# Sheet2.net
KiCad netlist of a schematic drawn in Altium Designer
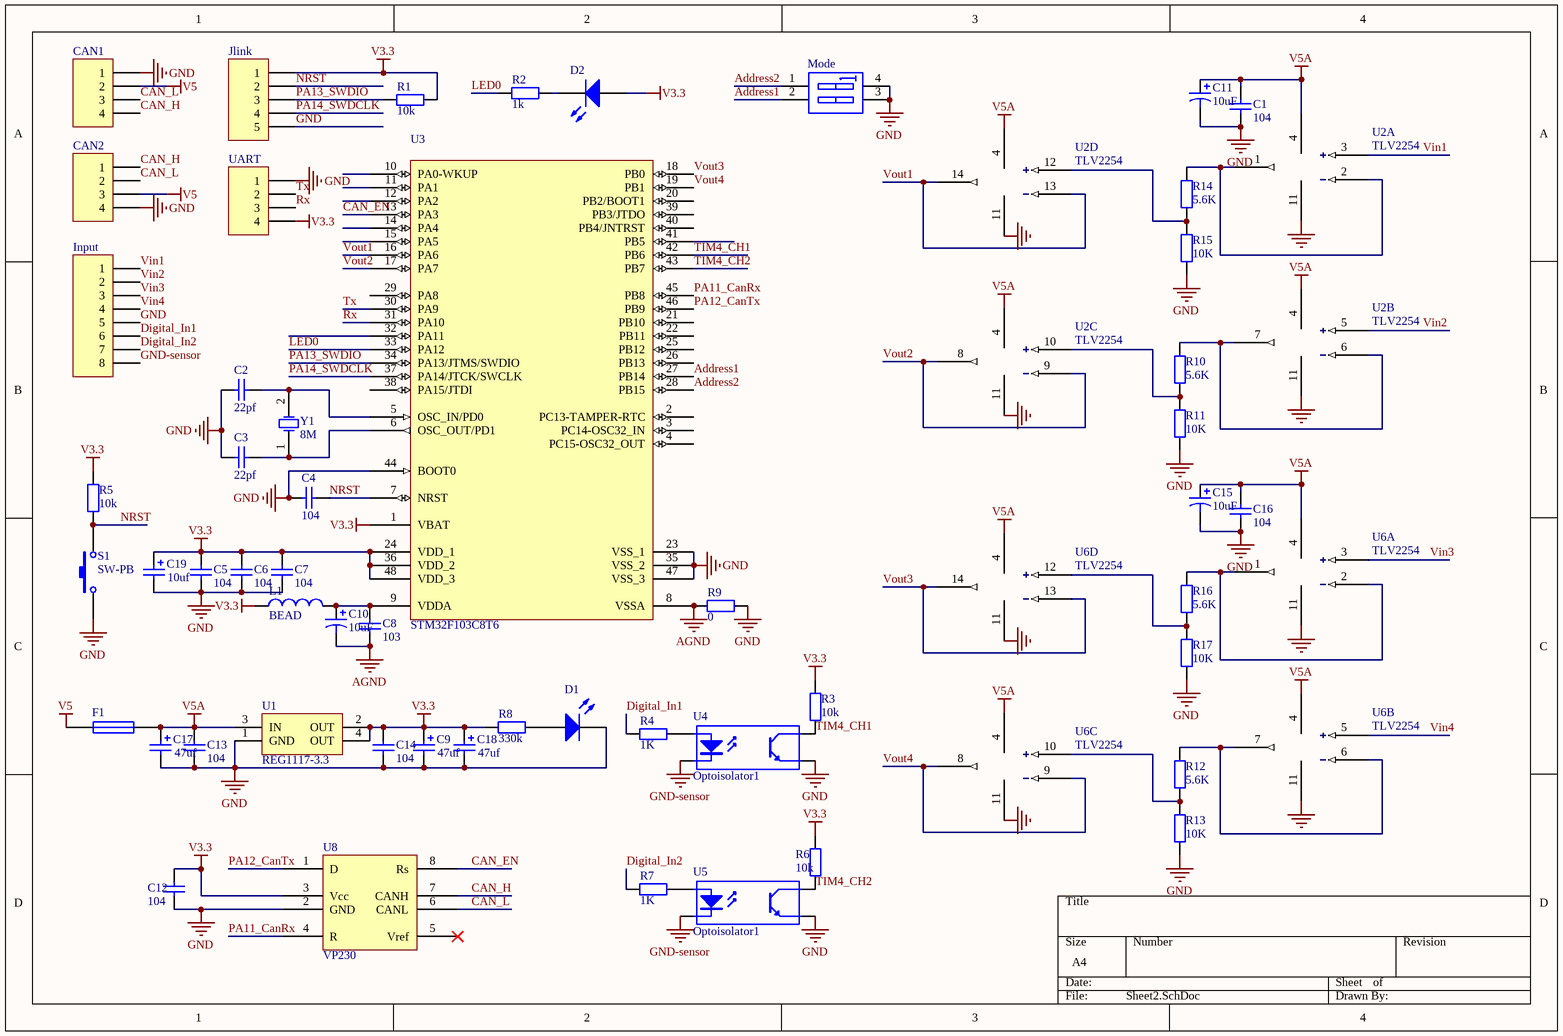
[diagram p0: Sheet2.SchDoc]

(export (version "E")
  (design (tool "Eeschema 10.0.6"))
  (components
    (comp (ref "C1")
      (value "104")
      (footprint "C0805")
      (description "Capacitor")
      (fields (field (name "Comment") "Cap") (field (name "PUBLISHER") "Altium Limited"))
      (libsource (lib "Miscellaneous Devices") (part "Cap"))
    )
    (comp (ref "C2")
      (value "22pf")
      (footprint "C0805")
      (description "Capacitor")
      (fields (field (name "Comment") "Cap") (field (name "PUBLISHER") "Altium Limited"))
      (libsource (lib "Miscellaneous Devices") (part "Cap"))
    )
    (comp (ref "C3")
      (value "22pf")
      (footprint "C0805")
      (description "Capacitor")
      (fields (field (name "Comment") "Cap") (field (name "PUBLISHER") "Altium Limited"))
      (libsource (lib "Miscellaneous Devices") (part "Cap"))
    )
    (comp (ref "C4")
      (value "104")
      (footprint "C0805")
      (description "Capacitor")
      (fields (field (name "Comment") "Cap") (field (name "PUBLISHER") "Altium Limited"))
      (libsource (lib "Miscellaneous Devices") (part "Cap"))
    )
    (comp (ref "C5")
      (value "104")
      (footprint "C0805")
      (description "Capacitor")
      (fields (field (name "Comment") "Cap") (field (name "PUBLISHER") "Altium Limited"))
      (libsource (lib "Miscellaneous Devices") (part "Cap"))
    )
    (comp (ref "C6")
      (value "104")
      (footprint "C0805")
      (description "Capacitor")
      (fields (field (name "Comment") "Cap") (field (name "PUBLISHER") "Altium Limited"))
      (libsource (lib "Miscellaneous Devices") (part "Cap"))
    )
    (comp (ref "C7")
      (value "104")
      (footprint "C0805")
      (description "Capacitor")
      (fields (field (name "Comment") "Cap") (field (name "PUBLISHER") "Altium Limited"))
      (libsource (lib "Miscellaneous Devices") (part "Cap"))
    )
    (comp (ref "C8")
      (value "103")
      (footprint "C0805")
      (description "Capacitor")
      (fields (field (name "Comment") "Cap") (field (name "PUBLISHER") "Altium Limited"))
      (libsource (lib "Miscellaneous Devices") (part "Cap"))
    )
    (comp (ref "C9")
      (value "47uf")
      (footprint "1812")
      (description "Polarized Capacitor (Axial)")
      (fields (field (name "Comment") "Cap Pol2") (field (name "PUBLISHER") "Altium Limited"))
      (libsource (lib "Miscellaneous Devices") (part "Cap Pol2"))
    )
    (comp (ref "C10")
      (value "10uF")
      (footprint "1206")
      (description "Polarized Capacitor (Radial)")
      (fields (field (name "Comment") "Cap Pol1") (field (name "PUBLISHER") "Altium Limited"))
      (libsource (lib "Miscellaneous Devices") (part "Cap Pol1"))
    )
    (comp (ref "C11")
      (value "10uF")
      (footprint "1206")
      (description "Polarized Capacitor (Radial)")
      (fields (field (name "Comment") "Cap Pol1") (field (name "PUBLISHER") "Altium Limited"))
      (libsource (lib "Miscellaneous Devices") (part "Cap Pol1"))
    )
    (comp (ref "C12")
      (value "104")
      (footprint "C0805")
      (description "Capacitor")
      (fields (field (name "Comment") "Cap") (field (name "PUBLISHER") "Altium Limited"))
      (libsource (lib "Miscellaneous Devices") (part "Cap"))
    )
    (comp (ref "C13")
      (value "104")
      (footprint "C0805")
      (description "Capacitor")
      (fields (field (name "Comment") "Cap") (field (name "PUBLISHER") "Altium Limited"))
      (libsource (lib "Miscellaneous Devices") (part "Cap"))
    )
    (comp (ref "C14")
      (value "104")
      (footprint "C0805")
      (description "Capacitor")
      (fields (field (name "Comment") "Cap") (field (name "PUBLISHER") "Altium Limited"))
      (libsource (lib "Miscellaneous Devices") (part "Cap"))
    )
    (comp (ref "C15")
      (value "10uF")
      (footprint "1206")
      (description "Polarized Capacitor (Radial)")
      (fields (field (name "Comment") "Cap Pol1") (field (name "PUBLISHER") "Altium Limited"))
      (libsource (lib "Miscellaneous Devices") (part "Cap Pol1"))
    )
    (comp (ref "C16")
      (value "104")
      (footprint "C0805")
      (description "Capacitor")
      (fields (field (name "Comment") "Cap") (field (name "PUBLISHER") "Altium Limited"))
      (libsource (lib "Miscellaneous Devices") (part "Cap"))
    )
    (comp (ref "C17")
      (value "47uf")
      (footprint "1812")
      (description "Polarized Capacitor (Axial)")
      (fields (field (name "Comment") "Cap Pol2") (field (name "PUBLISHER") "Altium Limited"))
      (libsource (lib "Miscellaneous Devices") (part "Cap Pol2"))
    )
    (comp (ref "C18")
      (value "47uf")
      (footprint "1812")
      (description "Polarized Capacitor (Axial)")
      (fields (field (name "Comment") "Cap Pol2") (field (name "PUBLISHER") "Altium Limited"))
      (libsource (lib "Miscellaneous Devices") (part "Cap Pol2"))
    )
    (comp (ref "C19")
      (value "10uf")
      (footprint "1206")
      (description "Polarized Capacitor (Axial)")
      (fields (field (name "Comment") "Cap Pol2") (field (name "PUBLISHER") "Altium Limited"))
      (libsource (lib "Miscellaneous Devices") (part "Cap Pol2"))
    )
    (comp (ref "CAN1")
      (value "Header 4")
      (footprint "DuraClik*4")
      (description "Header, 4-Pin")
      (fields (field (name "PUBLISHER") "Altium Limited"))
      (libsource (lib "Miscellaneous Connectors") (part "Header 4"))
    )
    (comp (ref "CAN2")
      (value "Header 4")
      (footprint "DuraClik*4")
      (description "Header, 4-Pin")
      (fields (field (name "PUBLISHER") "Altium Limited"))
      (libsource (lib "Miscellaneous Connectors") (part "Header 4"))
    )
    (comp (ref "D1")
      (value "LED2")
      (footprint "C0805")
      (description "Typical RED, GREEN, YELLOW, AMBER GaAs LED")
      (fields (field (name "PUBLISHER") "Altium Limited"))
      (libsource (lib "Miscellaneous Devices") (part "LED2"))
    )
    (comp (ref "D2")
      (value "LED2")
      (footprint "C0805")
      (description "Typical RED, GREEN, YELLOW, AMBER GaAs LED")
      (fields (field (name "PUBLISHER") "Altium Limited"))
      (libsource (lib "Miscellaneous Devices") (part "LED2"))
    )
    (comp (ref "F1")
      (value "Fuse 1")
      (footprint "1812")
      (description "Fuse")
      (fields (field (name "PUBLISHER") "Altium Limited"))
      (libsource (lib "Miscellaneous Devices") (part "Fuse 1"))
    )
    (comp (ref "Input")
      (value "Header 8")
      (footprint "DuraClik*8")
      (description "Header, 8-Pin")
      (fields (field (name "PUBLISHER") "Altium Limited"))
      (libsource (lib "Miscellaneous Connectors") (part "Header 8"))
    )
    (comp (ref "Jlink")
      (value "Jlink")
      (footprint "HDR1X5")
      (description "Header, 5-Pin")
      (fields (field (name "PUBLISHER") "Altium Limited"))
      (libsource (lib "Miscellaneous Connectors") (part "Header 5"))
    )
    (comp (ref "L1")
      (value "BEAD")
      (footprint "C0805")
      (description "Inductor")
      (fields (field (name "PUBLISHER") "Altium Limited"))
      (libsource (lib "Miscellaneous Devices") (part "Inductor"))
    )
    (comp (ref "Mode")
      (value "SW DIP-2")
      (footprint "DIP-4")
      (description "DIP Switch, 2 Position, SPST")
      (fields (field (name "PUBLISHER") "Altium Limited"))
      (libsource (lib "Miscellaneous Devices") (part "SW DIP-2"))
    )
    (comp (ref "R1")
      (value "10k")
      (footprint "C0805")
      (description "Resistor")
      (fields (field (name "Comment") "Res2") (field (name "PUBLISHER") "Altium Limited"))
      (libsource (lib "") (part "Res2_2"))
    )
    (comp (ref "R2")
      (value "1k")
      (footprint "C0805")
      (description "Resistor")
      (fields (field (name "Comment") "Res2") (field (name "PUBLISHER") "Altium Limited"))
      (libsource (lib "") (part "Res2_2"))
    )
    (comp (ref "R3")
      (value "10k")
      (footprint "C0805")
      (description "Resistor")
      (fields (field (name "Comment") "Res2") (field (name "PUBLISHER") "Altium Limited"))
      (libsource (lib "") (part "Res2_3"))
    )
    (comp (ref "R4")
      (value "1K")
      (footprint "C0805")
      (description "Resistor")
      (fields (field (name "Comment") "Res2") (field (name "PUBLISHER") "Altium Limited"))
      (libsource (lib "") (part "Res2_1"))
    )
    (comp (ref "R5")
      (value "10k")
      (footprint "C0805")
      (description "Resistor")
      (fields (field (name "Comment") "Res2") (field (name "PUBLISHER") "Altium Limited"))
      (libsource (lib "") (part "Res2_3"))
    )
    (comp (ref "R6")
      (value "10k")
      (footprint "C0805")
      (description "Resistor")
      (fields (field (name "Comment") "Res2") (field (name "PUBLISHER") "Altium Limited"))
      (libsource (lib "Miscellaneous Devices") (part "Res2"))
    )
    (comp (ref "R7")
      (value "1K")
      (footprint "C0805")
      (description "Resistor")
      (fields (field (name "Comment") "Res2") (field (name "PUBLISHER") "Altium Limited"))
      (libsource (lib "") (part "Res2_1"))
    )
    (comp (ref "R8")
      (value "330k")
      (footprint "C0805")
      (description "Resistor")
      (fields (field (name "Comment") "Res2") (field (name "PUBLISHER") "Altium Limited"))
      (libsource (lib "") (part "Res2_1"))
    )
    (comp (ref "R9")
      (value "0")
      (footprint "C0805")
      (description "Resistor")
      (fields (field (name "Comment") "Res2") (field (name "PUBLISHER") "Altium Limited"))
      (libsource (lib "") (part "Res2_1"))
    )
    (comp (ref "R10")
      (value "5.6K")
      (footprint "C0805")
      (description "Resistor")
      (fields (field (name "Comment") "Res2") (field (name "PUBLISHER") "Altium Limited"))
      (libsource (lib "Miscellaneous Devices") (part "Res2"))
    )
    (comp (ref "R11")
      (value "10K")
      (footprint "C0805")
      (description "Resistor")
      (fields (field (name "Comment") "Res2") (field (name "PUBLISHER") "Altium Limited"))
      (libsource (lib "Miscellaneous Devices") (part "Res2"))
    )
    (comp (ref "R12")
      (value "5.6K")
      (footprint "C0805")
      (description "Resistor")
      (fields (field (name "Comment") "Res2") (field (name "PUBLISHER") "Altium Limited"))
      (libsource (lib "Miscellaneous Devices") (part "Res2"))
    )
    (comp (ref "R13")
      (value "10K")
      (footprint "C0805")
      (description "Resistor")
      (fields (field (name "Comment") "Res2") (field (name "PUBLISHER") "Altium Limited"))
      (libsource (lib "Miscellaneous Devices") (part "Res2"))
    )
    (comp (ref "R14")
      (value "5.6K")
      (footprint "C0805")
      (description "Resistor")
      (fields (field (name "Comment") "Res2") (field (name "PUBLISHER") "Altium Limited"))
      (libsource (lib "Miscellaneous Devices") (part "Res2"))
    )
    (comp (ref "R15")
      (value "10K")
      (footprint "C0805")
      (description "Resistor")
      (fields (field (name "Comment") "Res2") (field (name "PUBLISHER") "Altium Limited"))
      (libsource (lib "Miscellaneous Devices") (part "Res2"))
    )
    (comp (ref "R16")
      (value "5.6K")
      (footprint "C0805")
      (description "Resistor")
      (fields (field (name "Comment") "Res2") (field (name "PUBLISHER") "Altium Limited"))
      (libsource (lib "Miscellaneous Devices") (part "Res2"))
    )
    (comp (ref "R17")
      (value "10K")
      (footprint "C0805")
      (description "Resistor")
      (fields (field (name "Comment") "Res2") (field (name "PUBLISHER") "Altium Limited"))
      (libsource (lib "Miscellaneous Devices") (part "Res2"))
    )
    (comp (ref "S1")
      (value "SW-PB")
      (footprint "button_SMD")
      (description "Switch")
      (fields (field (name "PUBLISHER") "Altium Limited"))
      (libsource (lib "Miscellaneous Devices") (part "SW-PB"))
    )
    (comp (ref "U1")
      (value "REG1117-3.3")
      (footprint "ZZ311")
      (description "800mA and 1A Low Dropout Positive Regulator 2.85V, 3.3V, 5V, and Adjustable")
      (fields (field (name "PUBLISHER") "Altium Limited"))
      (libsource (lib "BB Power Mgt Voltage Regulator") (part "REG1117-3.3"))
    )
    (comp (ref "U2") (value "TLV2254") (footprint "TSSOP14") (libsource (lib "can") (part "TLV2254")))
    (comp (ref "U3")
      (value "STM32F103C8T6")
      (footprint "LQFP48_N")
      (description "STM32 ARM-based 32-bit MCU with 64 Kbytes Flash, 48-pin LQFP, Industrial Temperature")
      (fields (field (name "PUBLISHER") "Altium Limited"))
      (libsource (lib "ST Microcontroller 32-Bit STM32") (part "STM32F103C8T6"))
    )
    (comp (ref "U4")
      (value "Optoisolator1")
      (footprint "SOP4-large")
      (description "4-Pin Phototransistor Optocoupler")
      (fields (field (name "PUBLISHER") "Altium Limited"))
      (libsource (lib "Miscellaneous Devices") (part "Optoisolator1"))
    )
    (comp (ref "U5")
      (value "Optoisolator1")
      (footprint "SOP4-large")
      (description "4-Pin Phototransistor Optocoupler")
      (fields (field (name "PUBLISHER") "Altium Limited"))
      (libsource (lib "Miscellaneous Devices") (part "Optoisolator1"))
    )
    (comp (ref "U6") (value "TLV2254") (footprint "TSSOP14") (libsource (lib "can") (part "TLV2254")))
    (comp (ref "U8")
      (value "VP230")
      (footprint "SOP127P600X175-8M")
      (description "3.3-VCANTRANSCEIVERS")
      (libsource (lib "can") (part "VP230"))
    )
    (comp (ref "UART")
      (value "Header 4")
      (footprint "HDR1X4")
      (description "Header, 4-Pin")
      (fields (field (name "PUBLISHER") "Altium Limited"))
      (libsource (lib "Miscellaneous Connectors") (part "Header 4"))
    )
    (comp (ref "Y1")
      (value "8M")
      (footprint "XTAL")
      (description "Crystal Oscillator")
      (fields (field (name "PUBLISHER") "Altium Limited"))
      (libsource (lib "Miscellaneous Devices") (part "XTAL"))
    )
  )
  (nets
    (net (code "1") (name "/Address1") (class "Default")
      (node (ref "Mode") (pin "2") (pinfunction "A2_2") (pintype "passive"))
      (node (ref "U3") (pin "27") (pinfunction "PB14_27") (pintype "bidirectional"))
    )
    (net (code "2") (name "/Address2") (class "Default")
      (node (ref "Mode") (pin "1") (pinfunction "A1_1") (pintype "passive"))
      (node (ref "U3") (pin "28") (pinfunction "PB15_28") (pintype "bidirectional"))
    )
    (net (code "3") (name "/CAN_EN") (class "Default")
      (node (ref "U3") (pin "13") (pinfunction "PA3_13") (pintype "bidirectional"))
      (node (ref "U8") (pin "8") (pinfunction "Rs_8") (pintype "passive"))
    )
    (net (code "4") (name "/CAN_H") (class "Default")
      (node (ref "CAN1") (pin "4") (pinfunction "4_4") (pintype "passive"))
      (node (ref "CAN2") (pin "1") (pinfunction "1_1") (pintype "passive"))
      (node (ref "U8") (pin "7") (pinfunction "CANH_7") (pintype "passive"))
    )
    (net (code "5") (name "/CAN_L") (class "Default")
      (node (ref "CAN1") (pin "3") (pinfunction "3_3") (pintype "passive"))
      (node (ref "CAN2") (pin "2") (pinfunction "2_2") (pintype "passive"))
      (node (ref "U8") (pin "6") (pinfunction "CANL_6") (pintype "passive"))
    )
    (net (code "6") (name "/Digital_In1") (class "Default")
      (node (ref "Input") (pin "6") (pinfunction "6_6") (pintype "passive"))
      (node (ref "R4") (pin "2") (pinfunction "2_2") (pintype "passive"))
    )
    (net (code "7") (name "/Digital_In2") (class "Default")
      (node (ref "Input") (pin "7") (pinfunction "7_7") (pintype "passive"))
      (node (ref "R7") (pin "2") (pinfunction "2_2") (pintype "passive"))
    )
    (net (code "8") (name "/LED0") (class "Default")
      (node (ref "R2") (pin "1") (pinfunction "1_1") (pintype "passive"))
      (node (ref "U3") (pin "33") (pinfunction "PA12_33") (pintype "bidirectional"))
    )
    (net (code "9") (name "/NRST") (class "Default")
      (node (ref "C4") (pin "2") (pinfunction "2_2") (pintype "passive"))
      (node (ref "Jlink") (pin "2") (pinfunction "2_2") (pintype "passive"))
      (node (ref "R5") (pin "2") (pinfunction "2_2") (pintype "passive"))
      (node (ref "S1") (pin "2") (pinfunction "2_2") (pintype "passive"))
      (node (ref "U3") (pin "7") (pinfunction "NRST_7") (pintype "bidirectional"))
    )
    (net (code "10") (name "/PA11_CanRx") (class "Default")
      (node (ref "U3") (pin "45") (pinfunction "PB8_45") (pintype "bidirectional"))
      (node (ref "U8") (pin "4") (pinfunction "R_4") (pintype "passive"))
    )
    (net (code "11") (name "/PA12_CanTx") (class "Default")
      (node (ref "U3") (pin "46") (pinfunction "PB9_46") (pintype "bidirectional"))
      (node (ref "U8") (pin "1") (pinfunction "D_1") (pintype "passive"))
    )
    (net (code "12") (name "/PA13_SWDIO") (class "Default")
      (node (ref "Jlink") (pin "3") (pinfunction "3_3") (pintype "passive"))
      (node (ref "R1") (pin "1") (pinfunction "1_1") (pintype "passive"))
      (node (ref "U3") (pin "34") (pinfunction "PA13/JTMS/SWDIO_34") (pintype "bidirectional"))
    )
    (net (code "13") (name "/PA14_SWDCLK") (class "Default")
      (node (ref "Jlink") (pin "4") (pinfunction "4_4") (pintype "passive"))
      (node (ref "U3") (pin "37") (pinfunction "PA14/JTCK/SWCLK_37") (pintype "bidirectional"))
    )
    (net (code "14") (name "/Rx") (class "Default")
      (node (ref "U3") (pin "31") (pinfunction "PA10_31") (pintype "bidirectional"))
      (node (ref "UART") (pin "3") (pinfunction "3_3") (pintype "passive"))
    )
    (net (code "15") (name "/TIM4_CH1") (class "Default")
      (node (ref "R3") (pin "2") (pinfunction "2_2") (pintype "passive"))
      (node (ref "U3") (pin "42") (pinfunction "PB6_42") (pintype "bidirectional"))
      (node (ref "U4") (pin "4") (pinfunction "C_4") (pintype "passive"))
    )
    (net (code "16") (name "/TIM4_CH2") (class "Default")
      (node (ref "R6") (pin "1") (pinfunction "1_1") (pintype "passive"))
      (node (ref "U3") (pin "43") (pinfunction "PB7_43") (pintype "bidirectional"))
      (node (ref "U5") (pin "4") (pinfunction "C_4") (pintype "passive"))
    )
    (net (code "17") (name "/Tx") (class "Default")
      (node (ref "U3") (pin "30") (pinfunction "PA9_30") (pintype "bidirectional"))
      (node (ref "UART") (pin "2") (pinfunction "2_2") (pintype "passive"))
    )
    (net (code "18") (name "/Vin1") (class "Default")
      (node (ref "Input") (pin "1") (pinfunction "1_1") (pintype "passive"))
      (node (ref "U2") (pin "3") (pinfunction "1IN+_3") (pintype "input"))
    )
    (net (code "19") (name "/Vin2") (class "Default")
      (node (ref "Input") (pin "2") (pinfunction "2_2") (pintype "passive"))
      (node (ref "U2") (pin "5") (pinfunction "2IN+_5") (pintype "input"))
    )
    (net (code "20") (name "/Vin3") (class "Default")
      (node (ref "Input") (pin "3") (pinfunction "3_3") (pintype "passive"))
      (node (ref "U6") (pin "3") (pinfunction "1IN+_3") (pintype "input"))
    )
    (net (code "21") (name "/Vin4") (class "Default")
      (node (ref "Input") (pin "4") (pinfunction "4_4") (pintype "passive"))
      (node (ref "U6") (pin "5") (pinfunction "2IN+_5") (pintype "input"))
    )
    (net (code "22") (name "/Vout1") (class "Default")
      (node (ref "U2") (pin "13") (pinfunction "4IN-_13") (pintype "input"))
      (node (ref "U2") (pin "14") (pinfunction "4OUT_14") (pintype "output"))
      (node (ref "U3") (pin "16") (pinfunction "PA6_16") (pintype "bidirectional"))
    )
    (net (code "23") (name "/Vout2") (class "Default")
      (node (ref "U2") (pin "8") (pinfunction "3OUT_8") (pintype "output"))
      (node (ref "U2") (pin "9") (pinfunction "3IN-_9") (pintype "input"))
      (node (ref "U3") (pin "17") (pinfunction "PA7_17") (pintype "bidirectional"))
    )
    (net (code "24") (name "/Vout3") (class "Default")
      (node (ref "U3") (pin "18") (pinfunction "PB0_18") (pintype "bidirectional"))
      (node (ref "U6") (pin "13") (pinfunction "4IN-_13") (pintype "input"))
      (node (ref "U6") (pin "14") (pinfunction "4OUT_14") (pintype "output"))
    )
    (net (code "25") (name "/Vout4") (class "Default")
      (node (ref "U3") (pin "19") (pinfunction "PB1_19") (pintype "bidirectional"))
      (node (ref "U6") (pin "8") (pinfunction "3OUT_8") (pintype "output"))
      (node (ref "U6") (pin "9") (pinfunction "3IN-_9") (pintype "input"))
    )
    (net (code "26") (name "AGND") (class "Default")
      (node (ref "C10") (pin "2") (pinfunction "2_2") (pintype "passive"))
      (node (ref "C8") (pin "2") (pinfunction "2_2") (pintype "passive"))
      (node (ref "R9") (pin "2") (pinfunction "2_2") (pintype "passive"))
      (node (ref "U3") (pin "8") (pinfunction "VSSA_8") (pintype "power_in"))
    )
    (net (code "27") (name "GND") (class "Default")
      (node (ref "C1") (pin "2") (pinfunction "2_2") (pintype "passive"))
      (node (ref "C11") (pin "2") (pinfunction "2_2") (pintype "passive"))
      (node (ref "C12") (pin "1") (pinfunction "1_1") (pintype "passive"))
      (node (ref "C13") (pin "2") (pinfunction "2_2") (pintype "passive"))
      (node (ref "C14") (pin "2") (pinfunction "2_2") (pintype "passive"))
      (node (ref "C15") (pin "2") (pinfunction "2_2") (pintype "passive"))
      (node (ref "C16") (pin "2") (pinfunction "2_2") (pintype "passive"))
      (node (ref "C17") (pin "2") (pinfunction "2_2") (pintype "passive"))
      (node (ref "C18") (pin "2") (pinfunction "2_2") (pintype "passive"))
      (node (ref "C19") (pin "2") (pinfunction "2_2") (pintype "passive"))
      (node (ref "C2") (pin "1") (pinfunction "1_1") (pintype "passive"))
      (node (ref "C3") (pin "1") (pinfunction "1_1") (pintype "passive"))
      (node (ref "C4") (pin "1") (pinfunction "1_1") (pintype "passive"))
      (node (ref "C5") (pin "2") (pinfunction "2_2") (pintype "passive"))
      (node (ref "C6") (pin "2") (pinfunction "2_2") (pintype "passive"))
      (node (ref "C7") (pin "2") (pinfunction "2_2") (pintype "passive"))
      (node (ref "C9") (pin "2") (pinfunction "2_2") (pintype "passive"))
      (node (ref "CAN1") (pin "1") (pinfunction "1_1") (pintype "passive"))
      (node (ref "CAN2") (pin "4") (pinfunction "4_4") (pintype "passive"))
      (node (ref "D1") (pin "2") (pinfunction "K_2") (pintype "passive"))
      (node (ref "Input") (pin "5") (pinfunction "5_5") (pintype "passive"))
      (node (ref "Jlink") (pin "5") (pinfunction "5_5") (pintype "passive"))
      (node (ref "Mode") (pin "3") (pinfunction "B2_3") (pintype "passive"))
      (node (ref "Mode") (pin "4") (pinfunction "B1_4") (pintype "passive"))
      (node (ref "R11") (pin "1") (pinfunction "1_1") (pintype "passive"))
      (node (ref "R13") (pin "1") (pinfunction "1_1") (pintype "passive"))
      (node (ref "R15") (pin "1") (pinfunction "1_1") (pintype "passive"))
      (node (ref "R17") (pin "1") (pinfunction "1_1") (pintype "passive"))
      (node (ref "R9") (pin "1") (pinfunction "1_1") (pintype "passive"))
      (node (ref "S1") (pin "1") (pinfunction "1_1") (pintype "passive"))
      (node (ref "U1") (pin "1") (pinfunction "GND_1") (pintype "power_in"))
      (node (ref "U2") (pin "11") (pinfunction "GND_11") (pintype "passive"))
      (node (ref "U3") (pin "23") (pinfunction "VSS_1_23") (pintype "power_in"))
      (node (ref "U3") (pin "35") (pinfunction "VSS_2_35") (pintype "power_in"))
      (node (ref "U3") (pin "44") (pinfunction "BOOT0_44") (pintype "input"))
      (node (ref "U3") (pin "47") (pinfunction "VSS_3_47") (pintype "power_in"))
      (node (ref "U4") (pin "3") (pinfunction "E_3") (pintype "passive"))
      (node (ref "U5") (pin "3") (pinfunction "E_3") (pintype "passive"))
      (node (ref "U6") (pin "11") (pinfunction "GND_11") (pintype "passive"))
      (node (ref "U8") (pin "2") (pinfunction "GND_2") (pintype "passive"))
      (node (ref "UART") (pin "1") (pinfunction "1_1") (pintype "passive"))
    )
    (net (code "28") (name "GND-sensor") (class "Default")
      (node (ref "Input") (pin "8") (pinfunction "8_8") (pintype "passive"))
      (node (ref "U4") (pin "2") (pinfunction "K_2") (pintype "passive"))
      (node (ref "U5") (pin "2") (pinfunction "K_2") (pintype "passive"))
    )
    (net (code "29") (name "Net-(D1-A)") (class "Default")
      (node (ref "D1") (pin "1") (pinfunction "A_1") (pintype "passive"))
      (node (ref "R8") (pin "1") (pinfunction "1_1") (pintype "passive"))
    )
    (net (code "30") (name "Net-(D2-K)") (class "Default")
      (node (ref "D2") (pin "2") (pinfunction "K_2") (pintype "passive"))
      (node (ref "R2") (pin "2") (pinfunction "2_2") (pintype "passive"))
    )
    (net (code "31") (name "Net-(U2A-1IN-)") (class "Default")
      (node (ref "R14") (pin "2") (pinfunction "2_2") (pintype "passive"))
      (node (ref "U2") (pin "1") (pinfunction "1OUT_1") (pintype "output"))
      (node (ref "U2") (pin "2") (pinfunction "1IN-_2") (pintype "input"))
    )
    (net (code "32") (name "Net-(U2B-2IN-)") (class "Default")
      (node (ref "R10") (pin "2") (pinfunction "2_2") (pintype "passive"))
      (node (ref "U2") (pin "6") (pinfunction "2IN-_6") (pintype "input"))
      (node (ref "U2") (pin "7") (pinfunction "2OUT_7") (pintype "output"))
    )
    (net (code "33") (name "Net-(U2C-3IN+)") (class "Default")
      (node (ref "R10") (pin "1") (pinfunction "1_1") (pintype "passive"))
      (node (ref "R11") (pin "2") (pinfunction "2_2") (pintype "passive"))
      (node (ref "U2") (pin "10") (pinfunction "3IN+_10") (pintype "input"))
    )
    (net (code "34") (name "Net-(U2D-4IN+)") (class "Default")
      (node (ref "R14") (pin "1") (pinfunction "1_1") (pintype "passive"))
      (node (ref "R15") (pin "2") (pinfunction "2_2") (pintype "passive"))
      (node (ref "U2") (pin "12") (pinfunction "4IN+_12") (pintype "input"))
    )
    (net (code "35") (name "Net-(U3-OSC_IN{slash}PD0)") (class "Default")
      (node (ref "C2") (pin "2") (pinfunction "2_2") (pintype "passive"))
      (node (ref "U3") (pin "5") (pinfunction "OSC_IN/PD0_5") (pintype "input"))
      (node (ref "Y1") (pin "2") (pinfunction "OSC2_2") (pintype "passive"))
    )
    (net (code "36") (name "Net-(U3-OSC_OUT{slash}PD1)") (class "Default")
      (node (ref "C3") (pin "2") (pinfunction "2_2") (pintype "passive"))
      (node (ref "U3") (pin "6") (pinfunction "OSC_OUT/PD1_6") (pintype "output"))
      (node (ref "Y1") (pin "1") (pinfunction "OSC1_1") (pintype "passive"))
    )
    (net (code "37") (name "Net-(U3-VDDA)") (class "Default")
      (node (ref "C10") (pin "1") (pinfunction "1_1") (pintype "passive"))
      (node (ref "C8") (pin "1") (pinfunction "1_1") (pintype "passive"))
      (node (ref "L1") (pin "2") (pinfunction "2_2") (pintype "passive"))
      (node (ref "U3") (pin "9") (pinfunction "VDDA_9") (pintype "power_in"))
    )
    (net (code "38") (name "Net-(U4-A)") (class "Default")
      (node (ref "R4") (pin "1") (pinfunction "1_1") (pintype "passive"))
      (node (ref "U4") (pin "1") (pinfunction "A_1") (pintype "passive"))
    )
    (net (code "39") (name "Net-(U5-A)") (class "Default")
      (node (ref "R7") (pin "1") (pinfunction "1_1") (pintype "passive"))
      (node (ref "U5") (pin "1") (pinfunction "A_1") (pintype "passive"))
    )
    (net (code "40") (name "Net-(U6A-1IN-)") (class "Default")
      (node (ref "R16") (pin "2") (pinfunction "2_2") (pintype "passive"))
      (node (ref "U6") (pin "1") (pinfunction "1OUT_1") (pintype "output"))
      (node (ref "U6") (pin "2") (pinfunction "1IN-_2") (pintype "input"))
    )
    (net (code "41") (name "Net-(U6B-2IN-)") (class "Default")
      (node (ref "R12") (pin "2") (pinfunction "2_2") (pintype "passive"))
      (node (ref "U6") (pin "6") (pinfunction "2IN-_6") (pintype "input"))
      (node (ref "U6") (pin "7") (pinfunction "2OUT_7") (pintype "output"))
    )
    (net (code "42") (name "Net-(U6C-3IN+)") (class "Default")
      (node (ref "R12") (pin "1") (pinfunction "1_1") (pintype "passive"))
      (node (ref "R13") (pin "2") (pinfunction "2_2") (pintype "passive"))
      (node (ref "U6") (pin "10") (pinfunction "3IN+_10") (pintype "input"))
    )
    (net (code "43") (name "Net-(U6D-4IN+)") (class "Default")
      (node (ref "R16") (pin "1") (pinfunction "1_1") (pintype "passive"))
      (node (ref "R17") (pin "2") (pinfunction "2_2") (pintype "passive"))
      (node (ref "U6") (pin "12") (pinfunction "4IN+_12") (pintype "input"))
    )
    (net (code "44") (name "V3.3") (class "Default")
      (node (ref "C12") (pin "2") (pinfunction "2_2") (pintype "passive"))
      (node (ref "C14") (pin "1") (pinfunction "1_1") (pintype "passive"))
      (node (ref "C18") (pin "1") (pinfunction "1_1") (pintype "passive"))
      (node (ref "C19") (pin "1") (pinfunction "1_1") (pintype "passive"))
      (node (ref "C5") (pin "1") (pinfunction "1_1") (pintype "passive"))
      (node (ref "C6") (pin "1") (pinfunction "1_1") (pintype "passive"))
      (node (ref "C7") (pin "1") (pinfunction "1_1") (pintype "passive"))
      (node (ref "C9") (pin "1") (pinfunction "1_1") (pintype "passive"))
      (node (ref "D2") (pin "1") (pinfunction "A_1") (pintype "passive"))
      (node (ref "Jlink") (pin "1") (pinfunction "1_1") (pintype "passive"))
      (node (ref "L1") (pin "1") (pinfunction "1_1") (pintype "passive"))
      (node (ref "R1") (pin "2") (pinfunction "2_2") (pintype "passive"))
      (node (ref "R3") (pin "1") (pinfunction "1_1") (pintype "passive"))
      (node (ref "R5") (pin "1") (pinfunction "1_1") (pintype "passive"))
      (node (ref "R6") (pin "2") (pinfunction "2_2") (pintype "passive"))
      (node (ref "R8") (pin "2") (pinfunction "2_2") (pintype "passive"))
      (node (ref "U1") (pin "2") (pinfunction "OUT_2") (pintype "power_in"))
      (node (ref "U1") (pin "4") (pinfunction "OUT_4") (pintype "power_in"))
      (node (ref "U3") (pin "1") (pinfunction "VBAT_1") (pintype "power_in"))
      (node (ref "U3") (pin "24") (pinfunction "VDD_1_24") (pintype "power_in"))
      (node (ref "U3") (pin "36") (pinfunction "VDD_2_36") (pintype "power_in"))
      (node (ref "U3") (pin "48") (pinfunction "VDD_3_48") (pintype "power_in"))
      (node (ref "U8") (pin "3") (pinfunction "Vcc_3") (pintype "passive"))
      (node (ref "UART") (pin "4") (pinfunction "4_4") (pintype "passive"))
    )
    (net (code "45") (name "V5") (class "Default")
      (node (ref "CAN1") (pin "2") (pinfunction "2_2") (pintype "passive"))
      (node (ref "CAN2") (pin "3") (pinfunction "3_3") (pintype "passive"))
      (node (ref "F1") (pin "2") (pinfunction "2_2") (pintype "passive"))
    )
    (net (code "46") (name "V5A") (class "Default")
      (node (ref "C1") (pin "1") (pinfunction "1_1") (pintype "passive"))
      (node (ref "C11") (pin "1") (pinfunction "1_1") (pintype "passive"))
      (node (ref "C13") (pin "1") (pinfunction "1_1") (pintype "passive"))
      (node (ref "C15") (pin "1") (pinfunction "1_1") (pintype "passive"))
      (node (ref "C16") (pin "1") (pinfunction "1_1") (pintype "passive"))
      (node (ref "C17") (pin "1") (pinfunction "1_1") (pintype "passive"))
      (node (ref "F1") (pin "1") (pinfunction "1_1") (pintype "passive"))
      (node (ref "U1") (pin "3") (pinfunction "IN_3") (pintype "power_in"))
      (node (ref "U2") (pin "4") (pinfunction "Vcc_4") (pintype "passive"))
      (node (ref "U6") (pin "4") (pinfunction "Vcc_4") (pintype "passive"))
    )
    (net (code "47") (name "unconnected-(U3-PA0-WKUP-Pad10)") (class "Default")
      (node (ref "U3") (pin "10") (pinfunction "PA0-WKUP_10") (pintype "bidirectional"))
    )
    (net (code "48") (name "unconnected-(U3-PA1-Pad11)") (class "Default")
      (node (ref "U3") (pin "11") (pinfunction "PA1_11") (pintype "bidirectional"))
    )
    (net (code "49") (name "unconnected-(U3-PA2-Pad12)") (class "Default")
      (node (ref "U3") (pin "12") (pinfunction "PA2_12") (pintype "bidirectional"))
    )
    (net (code "50") (name "unconnected-(U3-PA4-Pad14)") (class "Default")
      (node (ref "U3") (pin "14") (pinfunction "PA4_14") (pintype "bidirectional"))
    )
    (net (code "51") (name "unconnected-(U3-PA5-Pad15)") (class "Default")
      (node (ref "U3") (pin "15") (pinfunction "PA5_15") (pintype "bidirectional"))
    )
    (net (code "52") (name "unconnected-(U3-PA8-Pad29)") (class "Default")
      (node (ref "U3") (pin "29") (pinfunction "PA8_29") (pintype "bidirectional"))
    )
    (net (code "53") (name "unconnected-(U3-PA11-Pad32)") (class "Default")
      (node (ref "U3") (pin "32") (pinfunction "PA11_32") (pintype "bidirectional"))
    )
    (net (code "54") (name "unconnected-(U3-PA15{slash}JTDI-Pad38)") (class "Default")
      (node (ref "U3") (pin "38") (pinfunction "PA15/JTDI_38") (pintype "bidirectional"))
    )
    (net (code "55") (name "unconnected-(U3-PB2{slash}BOOT1-Pad20)") (class "Default")
      (node (ref "U3") (pin "20") (pinfunction "PB2/BOOT1_20") (pintype "bidirectional"))
    )
    (net (code "56") (name "unconnected-(U3-PB3{slash}JTDO-Pad39)") (class "Default")
      (node (ref "U3") (pin "39") (pinfunction "PB3/JTDO_39") (pintype "bidirectional"))
    )
    (net (code "57") (name "unconnected-(U3-PB4{slash}JNTRST-Pad40)") (class "Default")
      (node (ref "U3") (pin "40") (pinfunction "PB4/JNTRST_40") (pintype "bidirectional"))
    )
    (net (code "58") (name "unconnected-(U3-PB5-Pad41)") (class "Default")
      (node (ref "U3") (pin "41") (pinfunction "PB5_41") (pintype "bidirectional"))
    )
    (net (code "59") (name "unconnected-(U3-PB10-Pad21)") (class "Default")
      (node (ref "U3") (pin "21") (pinfunction "PB10_21") (pintype "bidirectional"))
    )
    (net (code "60") (name "unconnected-(U3-PB11-Pad22)") (class "Default")
      (node (ref "U3") (pin "22") (pinfunction "PB11_22") (pintype "bidirectional"))
    )
    (net (code "61") (name "unconnected-(U3-PB12-Pad25)") (class "Default")
      (node (ref "U3") (pin "25") (pinfunction "PB12_25") (pintype "bidirectional"))
    )
    (net (code "62") (name "unconnected-(U3-PB13-Pad26)") (class "Default")
      (node (ref "U3") (pin "26") (pinfunction "PB13_26") (pintype "bidirectional"))
    )
    (net (code "63") (name "unconnected-(U3-PC13-TAMPER-RTC-Pad2)") (class "Default")
      (node (ref "U3") (pin "2") (pinfunction "PC13-TAMPER-RTC_2") (pintype "bidirectional"))
    )
    (net (code "64") (name "unconnected-(U3-PC14-OSC32_IN-Pad3)") (class "Default")
      (node (ref "U3") (pin "3") (pinfunction "PC14-OSC32_IN_3") (pintype "bidirectional"))
    )
    (net (code "65") (name "unconnected-(U3-PC15-OSC32_OUT-Pad4)") (class "Default")
      (node (ref "U3") (pin "4") (pinfunction "PC15-OSC32_OUT_4") (pintype "bidirectional"))
    )
    (net (code "66") (name "unconnected-(U8-Vref-Pad5)") (class "Default")
      (node (ref "U8") (pin "5") (pinfunction "Vref_5") (pintype "passive+no_connect"))
    )
  )
)
